# brobot.net
KiCad netlist of a schematic drawn in EAGLE
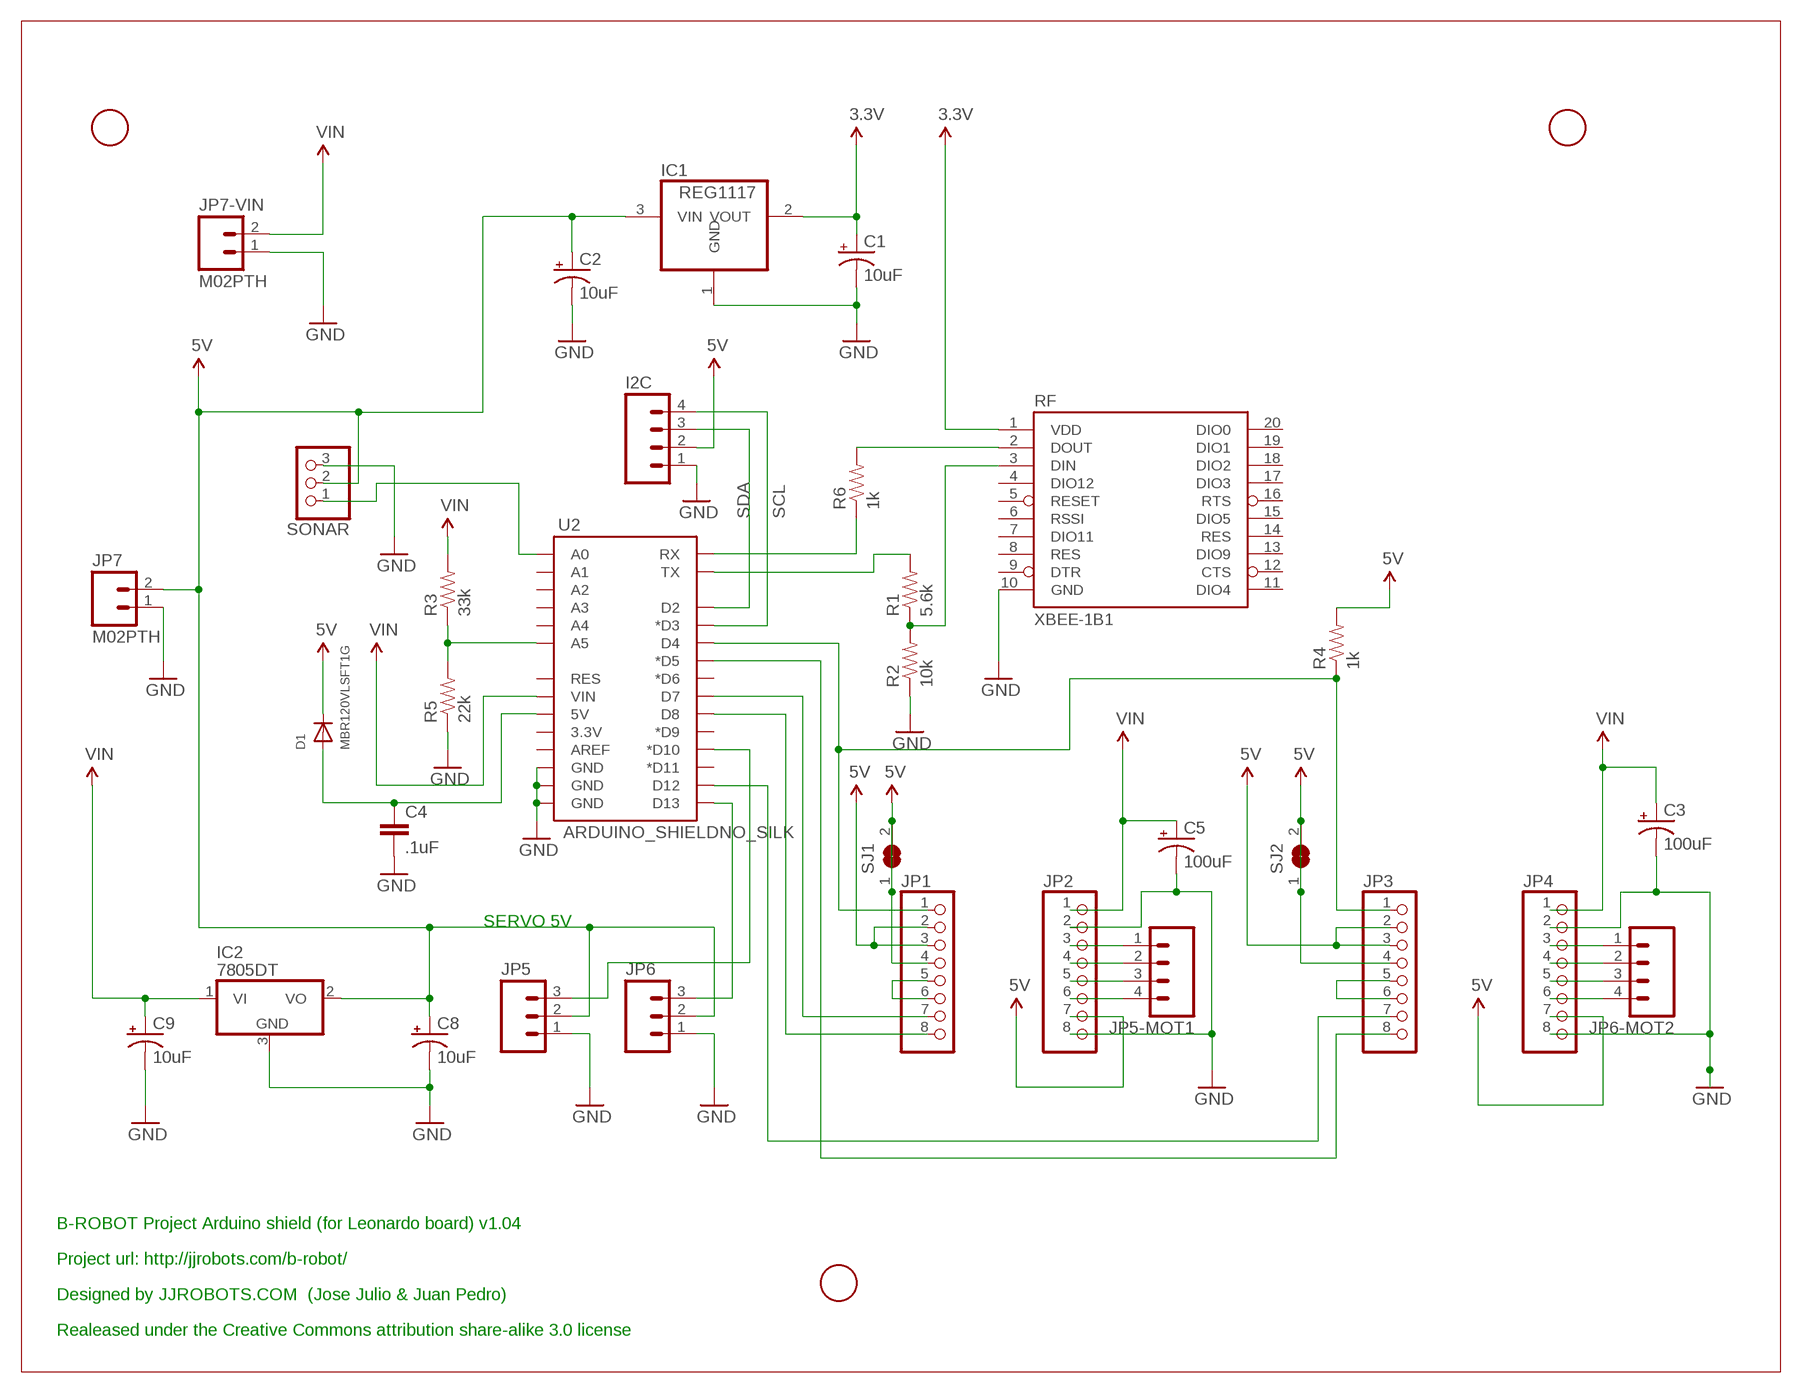
[diagram p0: schematic, sheet 1]

(export (version "E")
  (design (tool "Eeschema 10.0.6"))
  (components
    (comp (ref "C1")
      (value "10uF")
      (footprint "eagle-import:EIA3216")
      (libsource (lib "eagle-import") (part "CAP_POL1206"))
    )
    (comp (ref "C2")
      (value "10uF")
      (footprint "eagle-import:EIA3216")
      (libsource (lib "eagle-import") (part "CAP_POL1206"))
    )
    (comp (ref "C3")
      (value "100uF")
      (footprint "eagle-import:PANASONIC_D")
      (libsource (lib "eagle-import") (part "CAP_POLD"))
    )
    (comp (ref "C4")
      (value ".1uF")
      (footprint "eagle-import:0402-CAP")
      (libsource (lib "eagle-import") (part "CAP0402-CAP"))
    )
    (comp (ref "C5")
      (value "100uF")
      (footprint "eagle-import:PANASONIC_D")
      (libsource (lib "eagle-import") (part "CAP_POLD"))
    )
    (comp (ref "C8")
      (value "10uF")
      (footprint "eagle-import:EIA3216")
      (libsource (lib "eagle-import") (part "CAP_POL1206"))
    )
    (comp (ref "C9")
      (value "10uF")
      (footprint "eagle-import:EIA3216")
      (libsource (lib "eagle-import") (part "CAP_POL1206"))
    )
    (comp (ref "D1")
      (value "MBR120VLSFT1G")
      (footprint "eagle-import:SOD-123")
      (libsource (lib "eagle-import") (part "DIODESOD-123"))
    )
    (comp (ref "I2C")
      (value "M04PTH")
      (footprint "eagle-import:1X04")
      (libsource (lib "eagle-import") (part "M04PTH"))
    )
    (comp (ref "IC1")
      (value "REG1117")
      (footprint "eagle-import:SOT223")
      (libsource (lib "eagle-import") (part "REG1117"))
    )
    (comp (ref "IC2")
      (value "7805DT")
      (footprint "eagle-import:TO252")
      (libsource (lib "eagle-import") (part "78DT05"))
    )
    (comp (ref "JP1")
      (value "PINHD-1X8")
      (footprint "eagle-import:1X08")
      (libsource (lib "eagle-import") (part "PINHD-1X8"))
    )
    (comp (ref "JP2")
      (value "PINHD-1X8")
      (footprint "eagle-import:1X08")
      (libsource (lib "eagle-import") (part "PINHD-1X8"))
    )
    (comp (ref "JP3")
      (value "PINHD-1X8")
      (footprint "eagle-import:1X08")
      (libsource (lib "eagle-import") (part "PINHD-1X8"))
    )
    (comp (ref "JP4")
      (value "PINHD-1X8")
      (footprint "eagle-import:1X08")
      (libsource (lib "eagle-import") (part "PINHD-1X8"))
    )
    (comp (ref "JP5")
      (value "M03PTH")
      (footprint "eagle-import:1X03")
      (libsource (lib "eagle-import") (part "M03PTH"))
    )
    (comp (ref "JP5-MOT1")
      (value "M04PTH")
      (footprint "eagle-import:1X04")
      (libsource (lib "eagle-import") (part "M04PTH"))
    )
    (comp (ref "JP6")
      (value "M03PTH")
      (footprint "eagle-import:1X03")
      (libsource (lib "eagle-import") (part "M03PTH"))
    )
    (comp (ref "JP6-MOT2")
      (value "M04PTH")
      (footprint "eagle-import:1X04")
      (libsource (lib "eagle-import") (part "M04PTH"))
    )
    (comp (ref "JP7")
      (value "M02PTH")
      (footprint "eagle-import:1X02")
      (libsource (lib "eagle-import") (part "M02PTH"))
    )
    (comp (ref "JP7-VIN")
      (value "M02PTH")
      (footprint "eagle-import:1X02")
      (libsource (lib "eagle-import") (part "M02PTH"))
    )
    (comp (ref "R1")
      (value "5.6k")
      (footprint "eagle-import:0805")
      (libsource (lib "eagle-import") (part "RESISTOR0805-RES"))
    )
    (comp (ref "R2")
      (value "10k")
      (footprint "eagle-import:0805")
      (libsource (lib "eagle-import") (part "RESISTOR0805-RES"))
    )
    (comp (ref "R3")
      (value "33k")
      (footprint "eagle-import:0805")
      (libsource (lib "eagle-import") (part "RESISTOR0805-RES"))
    )
    (comp (ref "R4")
      (value "1k")
      (footprint "eagle-import:0805")
      (libsource (lib "eagle-import") (part "RESISTOR0805-RES"))
    )
    (comp (ref "R5")
      (value "22k")
      (footprint "eagle-import:0805")
      (libsource (lib "eagle-import") (part "RESISTOR0805-RES"))
    )
    (comp (ref "R6")
      (value "1k")
      (footprint "eagle-import:0805")
      (libsource (lib "eagle-import") (part "RESISTOR0805-RES"))
    )
    (comp (ref "RF")
      (value "XBEE-1B1")
      (footprint "eagle-import:XBEE-1")
      (libsource (lib "eagle-import") (part "XBEE-1B1"))
    )
    (comp (ref "SJ1")
      (value "SJW")
      (footprint "eagle-import:SJW")
      (libsource (lib "eagle-import") (part "SJW"))
    )
    (comp (ref "SJ2")
      (value "SJW")
      (footprint "eagle-import:SJW")
      (libsource (lib "eagle-import") (part "SJW"))
    )
    (comp (ref "SONAR")
      (value "PINHD-1X3")
      (footprint "eagle-import:1X03")
      (libsource (lib "eagle-import") (part "PINHD-1X3"))
    )
    (comp (ref "U$1")
      (value "FIDUCIAL")
      (footprint "eagle-import:FIDUCIAL_1MM")
      (libsource (lib "eagle-import") (part "FIDUCIAL"))
    )
    (comp (ref "U$2")
      (value "FIDUCIAL")
      (footprint "eagle-import:FIDUCIAL_1MM")
      (libsource (lib "eagle-import") (part "FIDUCIAL"))
    )
    (comp (ref "U$3")
      (value "FIDUCIAL")
      (footprint "eagle-import:FIDUCIAL_1MM")
      (libsource (lib "eagle-import") (part "FIDUCIAL"))
    )
    (comp (ref "U2")
      (value "ARDUINO_SHIELDNO_SILK")
      (footprint "eagle-import:DUEMILANOVE_VIAS")
      (libsource (lib "eagle-import") (part "ARDUINO_SHIELDNO_SILK"))
    )
  )
  (nets
    (net (code "1") (name "/SCL") (class "Default")
      (node (ref "I2C") (pin "4") (pinfunction "4_4") (pintype "passive"))
      (node (ref "U2") (pin "D3") (pinfunction "*D3_D3") (pintype "bidirectional"))
    )
    (net (code "2") (name "/SDA") (class "Default")
      (node (ref "I2C") (pin "3") (pinfunction "3_3") (pintype "passive"))
      (node (ref "U2") (pin "D2") (pinfunction "D2_D2") (pintype "bidirectional"))
    )
    (net (code "3") (name "3.3V") (class "Default")
      (node (ref "C1") (pin "A") (pinfunction "+_A") (pintype "passive"))
      (node (ref "IC1") (pin "2") (pinfunction "VOUT_2") (pintype "output"))
      (node (ref "RF") (pin "1") (pinfunction "VDD_1") (pintype "power_in"))
    )
    (net (code "4") (name "5V") (class "Default")
      (node (ref "C2") (pin "A") (pinfunction "+_A") (pintype "passive"))
      (node (ref "C8") (pin "A") (pinfunction "+_A") (pintype "passive"))
      (node (ref "D1") (pin "C") (pinfunction "C_C") (pintype "passive"))
      (node (ref "I2C") (pin "2") (pinfunction "2_2") (pintype "passive"))
      (node (ref "IC1") (pin "3") (pinfunction "VIN_3") (pintype "input"))
      (node (ref "IC2") (pin "2") (pinfunction "VO_2") (pintype "passive"))
      (node (ref "JP1") (pin "2") (pinfunction "2_2") (pintype "passive"))
      (node (ref "JP1") (pin "3") (pinfunction "3_3") (pintype "passive"))
      (node (ref "JP1") (pin "4") (pinfunction "4_4") (pintype "passive"))
      (node (ref "JP2") (pin "7") (pinfunction "7_7") (pintype "passive"))
      (node (ref "JP3") (pin "2") (pinfunction "2_2") (pintype "passive"))
      (node (ref "JP3") (pin "3") (pinfunction "3_3") (pintype "passive"))
      (node (ref "JP3") (pin "4") (pinfunction "4_4") (pintype "passive"))
      (node (ref "JP4") (pin "7") (pinfunction "7_7") (pintype "passive"))
      (node (ref "JP5") (pin "2") (pinfunction "2_2") (pintype "passive"))
      (node (ref "JP6") (pin "2") (pinfunction "2_2") (pintype "passive"))
      (node (ref "JP7") (pin "2") (pinfunction "2_2") (pintype "passive"))
      (node (ref "R4") (pin "2") (pinfunction "2_2") (pintype "passive"))
      (node (ref "SJ1") (pin "1") (pinfunction "1_1") (pintype "passive"))
      (node (ref "SJ1") (pin "2") (pinfunction "2_2") (pintype "passive"))
      (node (ref "SJ2") (pin "1") (pinfunction "1_1") (pintype "passive"))
      (node (ref "SJ2") (pin "2") (pinfunction "2_2") (pintype "passive"))
      (node (ref "SONAR") (pin "2") (pinfunction "2_2") (pintype "passive"))
    )
    (net (code "5") (name "GND") (class "Default")
      (node (ref "C1") (pin "C") (pinfunction "-_C") (pintype "passive"))
      (node (ref "C2") (pin "C") (pinfunction "-_C") (pintype "passive"))
      (node (ref "C3") (pin "-") (pinfunction "-_-") (pintype "passive"))
      (node (ref "C4") (pin "2") (pinfunction "2_2") (pintype "passive"))
      (node (ref "C5") (pin "-") (pinfunction "-_-") (pintype "passive"))
      (node (ref "C8") (pin "C") (pinfunction "-_C") (pintype "passive"))
      (node (ref "C9") (pin "C") (pinfunction "-_C") (pintype "passive"))
      (node (ref "I2C") (pin "1") (pinfunction "1_1") (pintype "passive"))
      (node (ref "IC1") (pin "1") (pinfunction "GND_1") (pintype "power_in"))
      (node (ref "IC2") (pin "3") (pinfunction "GND_3") (pintype "passive"))
      (node (ref "JP2") (pin "2") (pinfunction "2_2") (pintype "passive"))
      (node (ref "JP2") (pin "8") (pinfunction "8_8") (pintype "passive"))
      (node (ref "JP4") (pin "2") (pinfunction "2_2") (pintype "passive"))
      (node (ref "JP4") (pin "8") (pinfunction "8_8") (pintype "passive"))
      (node (ref "JP5") (pin "1") (pinfunction "1_1") (pintype "passive"))
      (node (ref "JP6") (pin "1") (pinfunction "1_1") (pintype "passive"))
      (node (ref "JP7") (pin "1") (pinfunction "1_1") (pintype "passive"))
      (node (ref "JP7-VIN") (pin "1") (pinfunction "1_1") (pintype "passive"))
      (node (ref "R2") (pin "1") (pinfunction "1_1") (pintype "passive"))
      (node (ref "R5") (pin "1") (pinfunction "1_1") (pintype "passive"))
      (node (ref "RF") (pin "10") (pinfunction "GND_10") (pintype "power_in"))
      (node (ref "SONAR") (pin "3") (pinfunction "3_3") (pintype "passive"))
      (node (ref "U2") (pin "GND@0") (pinfunction "GND_GND@0") (pintype "bidirectional"))
      (node (ref "U2") (pin "GND@1") (pinfunction "GND_GND@1") (pintype "bidirectional"))
      (node (ref "U2") (pin "GND@2") (pinfunction "GND_GND@2") (pintype "bidirectional"))
    )
    (net (code "6") (name "Net-(C4-Pad1)") (class "Default")
      (node (ref "C4") (pin "1") (pinfunction "1_1") (pintype "passive"))
      (node (ref "D1") (pin "A") (pinfunction "A_A") (pintype "passive"))
      (node (ref "U2") (pin "5V") (pinfunction "5V_5V") (pintype "bidirectional"))
    )
    (net (code "7") (name "Net-(JP1-Pad1)") (class "Default")
      (node (ref "JP1") (pin "1") (pinfunction "1_1") (pintype "passive"))
      (node (ref "JP3") (pin "1") (pinfunction "1_1") (pintype "passive"))
      (node (ref "R4") (pin "1") (pinfunction "1_1") (pintype "passive"))
      (node (ref "U2") (pin "D4") (pinfunction "D4_D4") (pintype "bidirectional"))
    )
    (net (code "8") (name "Net-(JP1-Pad5)") (class "Default")
      (node (ref "JP1") (pin "5") (pinfunction "5_5") (pintype "passive"))
      (node (ref "JP1") (pin "6") (pinfunction "6_6") (pintype "passive"))
    )
    (net (code "9") (name "Net-(JP1-Pad7)") (class "Default")
      (node (ref "JP1") (pin "7") (pinfunction "7_7") (pintype "passive"))
      (node (ref "U2") (pin "D7") (pinfunction "D7_D7") (pintype "bidirectional"))
    )
    (net (code "10") (name "Net-(JP1-Pad8)") (class "Default")
      (node (ref "JP1") (pin "8") (pinfunction "8_8") (pintype "passive"))
      (node (ref "U2") (pin "D8") (pinfunction "D8_D8") (pintype "bidirectional"))
    )
    (net (code "11") (name "Net-(JP2-Pad3)") (class "Default")
      (node (ref "JP2") (pin "3") (pinfunction "3_3") (pintype "passive"))
      (node (ref "JP5-MOT1") (pin "1") (pinfunction "1_1") (pintype "passive"))
    )
    (net (code "12") (name "Net-(JP2-Pad4)") (class "Default")
      (node (ref "JP2") (pin "4") (pinfunction "4_4") (pintype "passive"))
      (node (ref "JP5-MOT1") (pin "2") (pinfunction "2_2") (pintype "passive"))
    )
    (net (code "13") (name "Net-(JP2-Pad5)") (class "Default")
      (node (ref "JP2") (pin "5") (pinfunction "5_5") (pintype "passive"))
      (node (ref "JP5-MOT1") (pin "3") (pinfunction "3_3") (pintype "passive"))
    )
    (net (code "14") (name "Net-(JP2-Pad6)") (class "Default")
      (node (ref "JP2") (pin "6") (pinfunction "6_6") (pintype "passive"))
      (node (ref "JP5-MOT1") (pin "4") (pinfunction "4_4") (pintype "passive"))
    )
    (net (code "15") (name "Net-(JP3-Pad5)") (class "Default")
      (node (ref "JP3") (pin "5") (pinfunction "5_5") (pintype "passive"))
      (node (ref "JP3") (pin "6") (pinfunction "6_6") (pintype "passive"))
    )
    (net (code "16") (name "Net-(JP3-Pad7)") (class "Default")
      (node (ref "JP3") (pin "7") (pinfunction "7_7") (pintype "passive"))
      (node (ref "U2") (pin "D12") (pinfunction "D12_D12") (pintype "bidirectional"))
    )
    (net (code "17") (name "Net-(JP4-Pad3)") (class "Default")
      (node (ref "JP4") (pin "3") (pinfunction "3_3") (pintype "passive"))
      (node (ref "JP6-MOT2") (pin "1") (pinfunction "1_1") (pintype "passive"))
    )
    (net (code "18") (name "Net-(JP4-Pad4)") (class "Default")
      (node (ref "JP4") (pin "4") (pinfunction "4_4") (pintype "passive"))
      (node (ref "JP6-MOT2") (pin "2") (pinfunction "2_2") (pintype "passive"))
    )
    (net (code "19") (name "Net-(JP4-Pad5)") (class "Default")
      (node (ref "JP4") (pin "5") (pinfunction "5_5") (pintype "passive"))
      (node (ref "JP6-MOT2") (pin "3") (pinfunction "3_3") (pintype "passive"))
    )
    (net (code "20") (name "Net-(JP4-Pad6)") (class "Default")
      (node (ref "JP4") (pin "6") (pinfunction "6_6") (pintype "passive"))
      (node (ref "JP6-MOT2") (pin "4") (pinfunction "4_4") (pintype "passive"))
    )
    (net (code "21") (name "Net-(JP6-Pad3)") (class "Default")
      (node (ref "JP6") (pin "3") (pinfunction "3_3") (pintype "passive"))
      (node (ref "U2") (pin "D13") (pinfunction "D13_D13") (pintype "bidirectional"))
    )
    (net (code "22") (name "Net-(R1-Pad2)") (class "Default")
      (node (ref "R1") (pin "2") (pinfunction "2_2") (pintype "passive"))
      (node (ref "U2") (pin "TX") (pinfunction "TX_TX") (pintype "bidirectional"))
    )
    (net (code "23") (name "Net-(R3-Pad1)") (class "Default")
      (node (ref "R3") (pin "1") (pinfunction "1_1") (pintype "passive"))
      (node (ref "R5") (pin "2") (pinfunction "2_2") (pintype "passive"))
      (node (ref "U2") (pin "A5") (pinfunction "A5_A5") (pintype "bidirectional"))
    )
    (net (code "24") (name "Net-(R6-Pad1)") (class "Default")
      (node (ref "R6") (pin "1") (pinfunction "1_1") (pintype "passive"))
      (node (ref "U2") (pin "RX") (pinfunction "RX_RX") (pintype "bidirectional"))
    )
    (net (code "25") (name "Net-(RF-DIN)") (class "Default")
      (node (ref "R1") (pin "1") (pinfunction "1_1") (pintype "passive"))
      (node (ref "R2") (pin "2") (pinfunction "2_2") (pintype "passive"))
      (node (ref "RF") (pin "3") (pinfunction "DIN_3") (pintype "input"))
    )
    (net (code "26") (name "Net-(RF-DOUT)") (class "Default")
      (node (ref "R6") (pin "2") (pinfunction "2_2") (pintype "passive"))
      (node (ref "RF") (pin "2") (pinfunction "DOUT_2") (pintype "output"))
    )
    (net (code "27") (name "Net-(SONAR-Pad1)") (class "Default")
      (node (ref "SONAR") (pin "1") (pinfunction "1_1") (pintype "passive"))
      (node (ref "U2") (pin "A0") (pinfunction "A0_A0") (pintype "bidirectional"))
    )
    (net (code "28") (name "Net-(U2-*D5)") (class "Default")
      (node (ref "JP3") (pin "8") (pinfunction "8_8") (pintype "passive"))
      (node (ref "U2") (pin "D5") (pinfunction "*D5_D5") (pintype "bidirectional"))
    )
    (net (code "29") (name "Net-(U2-*D10)") (class "Default")
      (node (ref "JP5") (pin "3") (pinfunction "3_3") (pintype "passive"))
      (node (ref "U2") (pin "D10") (pinfunction "*D10_D10") (pintype "bidirectional"))
    )
    (net (code "30") (name "VIN") (class "Default")
      (node (ref "C3") (pin "+") (pinfunction "+_+") (pintype "passive"))
      (node (ref "C5") (pin "+") (pinfunction "+_+") (pintype "passive"))
      (node (ref "C9") (pin "A") (pinfunction "+_A") (pintype "passive"))
      (node (ref "IC2") (pin "1") (pinfunction "VI_1") (pintype "input"))
      (node (ref "JP2") (pin "1") (pinfunction "1_1") (pintype "passive"))
      (node (ref "JP4") (pin "1") (pinfunction "1_1") (pintype "passive"))
      (node (ref "JP7-VIN") (pin "2") (pinfunction "2_2") (pintype "passive"))
      (node (ref "R3") (pin "2") (pinfunction "2_2") (pintype "passive"))
      (node (ref "U2") (pin "VIN") (pinfunction "VIN_VIN") (pintype "bidirectional"))
    )
    (net (code "31") (name "unconnected-(RF-CTS-Pad12)") (class "Default")
      (node (ref "RF") (pin "12") (pinfunction "CTS_12") (pintype "output"))
    )
    (net (code "32") (name "unconnected-(RF-DIO0-Pad20)") (class "Default")
      (node (ref "RF") (pin "20") (pinfunction "DIO0_20") (pintype "bidirectional"))
    )
    (net (code "33") (name "unconnected-(RF-DIO1-Pad19)") (class "Default")
      (node (ref "RF") (pin "19") (pinfunction "DIO1_19") (pintype "bidirectional"))
    )
    (net (code "34") (name "unconnected-(RF-DIO2-Pad18)") (class "Default")
      (node (ref "RF") (pin "18") (pinfunction "DIO2_18") (pintype "bidirectional"))
    )
    (net (code "35") (name "unconnected-(RF-DIO3-Pad17)") (class "Default")
      (node (ref "RF") (pin "17") (pinfunction "DIO3_17") (pintype "bidirectional"))
    )
    (net (code "36") (name "unconnected-(RF-DIO4-Pad11)") (class "Default")
      (node (ref "RF") (pin "11") (pinfunction "DIO4_11") (pintype "bidirectional"))
    )
    (net (code "37") (name "unconnected-(RF-DIO5-Pad15)") (class "Default")
      (node (ref "RF") (pin "15") (pinfunction "DIO5_15") (pintype "bidirectional"))
    )
    (net (code "38") (name "unconnected-(RF-DIO9-Pad13)") (class "Default")
      (node (ref "RF") (pin "13") (pinfunction "DIO9_13") (pintype "bidirectional"))
    )
    (net (code "39") (name "unconnected-(RF-DIO11-Pad7)") (class "Default")
      (node (ref "RF") (pin "7") (pinfunction "DIO11_7") (pintype "bidirectional"))
    )
    (net (code "40") (name "unconnected-(RF-DIO12-Pad4)") (class "Default")
      (node (ref "RF") (pin "4") (pinfunction "DIO12_4") (pintype "bidirectional"))
    )
    (net (code "41") (name "unconnected-(RF-DTR-Pad9)") (class "Default")
      (node (ref "RF") (pin "9") (pinfunction "DTR_9") (pintype "bidirectional"))
    )
    (net (code "42") (name "unconnected-(RF-RES-Pad8)") (class "Default")
      (node (ref "RF") (pin "8") (pinfunction "RES_8") (pintype "bidirectional"))
    )
    (net (code "43") (name "unconnected-(RF-RES-Pad14)") (class "Default")
      (node (ref "RF") (pin "14") (pinfunction "RES_14") (pintype "bidirectional"))
    )
    (net (code "44") (name "unconnected-(RF-RESET-Pad5)") (class "Default")
      (node (ref "RF") (pin "5") (pinfunction "RESET_5") (pintype "input"))
    )
    (net (code "45") (name "unconnected-(RF-RSSI-Pad6)") (class "Default")
      (node (ref "RF") (pin "6") (pinfunction "RSSI_6") (pintype "bidirectional"))
    )
    (net (code "46") (name "unconnected-(RF-RTS-Pad16)") (class "Default")
      (node (ref "RF") (pin "16") (pinfunction "RTS_16") (pintype "input"))
    )
    (net (code "47") (name "unconnected-(U2-*D6-PadD6)") (class "Default")
      (node (ref "U2") (pin "D6") (pinfunction "*D6_D6") (pintype "bidirectional"))
    )
    (net (code "48") (name "unconnected-(U2-*D9-PadD9)") (class "Default")
      (node (ref "U2") (pin "D9") (pinfunction "*D9_D9") (pintype "bidirectional"))
    )
    (net (code "49") (name "unconnected-(U2-*D11-PadD11)") (class "Default")
      (node (ref "U2") (pin "D11") (pinfunction "*D11_D11") (pintype "bidirectional"))
    )
    (net (code "50") (name "unconnected-(U2-Pad3.3V)") (class "Default")
      (node (ref "U2") (pin "3.3V") (pinfunction "3.3V_3.3V") (pintype "bidirectional"))
    )
    (net (code "51") (name "unconnected-(U2-PadA1)") (class "Default")
      (node (ref "U2") (pin "A1") (pinfunction "A1_A1") (pintype "bidirectional"))
    )
    (net (code "52") (name "unconnected-(U2-PadA2)") (class "Default")
      (node (ref "U2") (pin "A2") (pinfunction "A2_A2") (pintype "bidirectional"))
    )
    (net (code "53") (name "unconnected-(U2-PadA3)") (class "Default")
      (node (ref "U2") (pin "A3") (pinfunction "A3_A3") (pintype "bidirectional"))
    )
    (net (code "54") (name "unconnected-(U2-PadA4)") (class "Default")
      (node (ref "U2") (pin "A4") (pinfunction "A4_A4") (pintype "bidirectional"))
    )
    (net (code "55") (name "unconnected-(U2-PadAREF)") (class "Default")
      (node (ref "U2") (pin "AREF") (pinfunction "AREF_AREF") (pintype "bidirectional"))
    )
    (net (code "56") (name "unconnected-(U2-PadRES)") (class "Default")
      (node (ref "U2") (pin "RES") (pinfunction "RES_RES") (pintype "bidirectional"))
    )
  )
)
